# HapticFeedback.net
KiCad netlist of a schematic drawn in Altium Designer
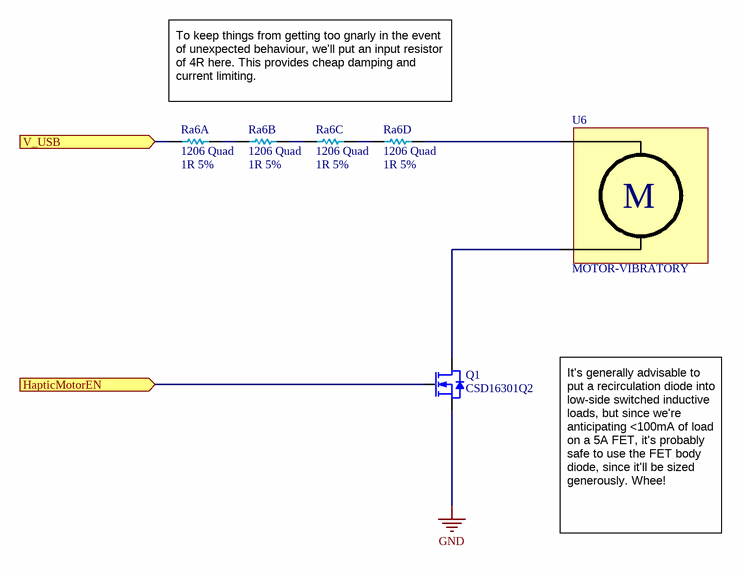
[diagram p0: HapticFeedback.SchDoc]

(export (version "E")
  (design (tool "Eeschema 10.0.6"))
  (components
    (comp (ref "Q1")
      (value "CSD16301Q2")
      (footprint "CSD16301Q2 - SON65P200X80_HS-7M")
      (description "25-V N-Channel Power MOSFET, 20mOhm, 2nC Qg")
      (libsource (lib "FETs") (part "CSD16301Q2"))
    )
    (comp (ref "Ra6")
      (value "1206 Quad")
      (footprint "4x 1R 5% - CAC-80P320X160-8M")
      (description "Chip resistor")
      (fields (field (name "ALTIUM_VALUE") "1R 5%"))
      (libsource (lib "Chip_Passives") (part "Quad Res 1R 5% 1206"))
    )
    (comp (ref "U6")
      (value "MOTOR-VIBRATORY")
      (footprint "MOTOR-VIBRATORY")
      (libsource (lib "Motors") (part "MOTOR-VIBRATORY"))
    )
  )
  (nets
    (net (code "1") (name "/HapticMotorEN") (class "Default")
      (node (ref "Q1") (pin "G") (pinfunction "G_G") (pintype "passive"))
    )
    (net (code "2") (name "/V_USB") (class "Default")
      (node (ref "Ra6") (pin "1") (pinfunction "1_1") (pintype "passive"))
    )
    (net (code "3") (name "GND") (class "Default")
      (node (ref "Q1") (pin "S") (pinfunction "S_S") (pintype "passive"))
    )
    (net (code "4") (name "Net-(Q1-PadD)") (class "Default")
      (node (ref "Q1") (pin "D") (pinfunction "D_D") (pintype "passive"))
      (node (ref "U6") (pin "2") (pinfunction "2_2") (pintype "passive"))
    )
    (net (code "5") (name "Net-(Ra6-Pad2)") (class "Default")
      (node (ref "Ra6") (pin "2") (pinfunction "2_2") (pintype "passive"))
      (node (ref "Ra6") (pin "8") (pinfunction "8_8") (pintype "passive"))
    )
    (net (code "6") (name "Net-(Ra6-Pad3)") (class "Default")
      (node (ref "Ra6") (pin "3") (pinfunction "3_3") (pintype "passive"))
      (node (ref "Ra6") (pin "7") (pinfunction "7_7") (pintype "passive"))
    )
    (net (code "7") (name "Net-(Ra6-Pad4)") (class "Default")
      (node (ref "Ra6") (pin "4") (pinfunction "4_4") (pintype "passive"))
      (node (ref "Ra6") (pin "6") (pinfunction "6_6") (pintype "passive"))
    )
    (net (code "8") (name "Net-(Ra6-Pad5)") (class "Default")
      (node (ref "Ra6") (pin "5") (pinfunction "5_5") (pintype "passive"))
      (node (ref "U6") (pin "1") (pinfunction "1_1") (pintype "passive"))
    )
  )
)
